# QSPI.net
KiCad netlist of a schematic drawn in Altium Designer
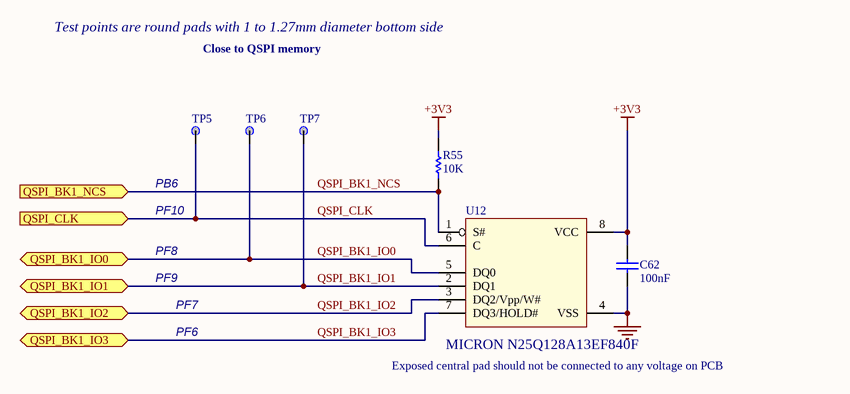
[diagram p0: QSPI.SchDoc]

(export (version "E")
  (design (tool "Eeschema 10.0.6"))
  (components
    (comp (ref "C62")
      (value "100nF")
      (footprint "0402C")
      (description "Capacitor")
      (fields (field (name "PUBLISHER") "Altium Limited"))
      (libsource (lib "Miscellaneous Devices") (part "Cap"))
    )
    (comp (ref "R55")
      (value "10K")
      (footprint "0402R")
      (description "Resistor,10K,0402,1%,YAGEO")
      (libsource (lib "MCD_TOOLS") (part "Res_10K_1%_0402"))
    )
    (comp (ref "TP5") (value "TP") (footprint "TP_C40") (libsource (lib "Almos") (part "TP")))
    (comp (ref "TP6") (value "TP") (footprint "TP_C40") (libsource (lib "Almos") (part "TP")))
    (comp (ref "TP7") (value "TP") (footprint "TP_C40") (libsource (lib "Almos") (part "TP")))
    (comp (ref "U12")
      (value "MICRON N25Q128A13EF840F")
      (footprint "DFN8_1R27_6X8_TP4R8X5R8")
      (description "128Mb, 3V, Multiple I/O Serial Flash Memory, Quad/Dual")
      (libsource (lib "MCD_TOOLS") (part "N25Q128A13EF840E"))
    )
  )
  (nets
    (net (code "1") (name "+3V3") (class "Default")
      (node (ref "C62") (pin "1") (pinfunction "1_1") (pintype "passive"))
      (node (ref "R55") (pin "2") (pinfunction "2_2") (pintype "passive"))
      (node (ref "U12") (pin "8") (pinfunction "VCC_8") (pintype "passive"))
    )
    (net (code "2") (name "/QSPI_BK1_IO0") (class "Default")
      (node (ref "TP6") (pin "1") (pinfunction "1_1") (pintype "passive"))
      (node (ref "U12") (pin "5") (pinfunction "DQ0_5") (pintype "passive"))
    )
    (net (code "3") (name "/QSPI_BK1_IO1") (class "Default")
      (node (ref "TP7") (pin "1") (pinfunction "1_1") (pintype "passive"))
      (node (ref "U12") (pin "2") (pinfunction "DQ1_2") (pintype "passive"))
    )
    (net (code "4") (name "/QSPI_BK1_IO2") (class "Default")
      (node (ref "U12") (pin "3") (pinfunction "DQ2/Vpp/W#_3") (pintype "passive"))
    )
    (net (code "5") (name "/QSPI_BK1_IO3") (class "Default")
      (node (ref "U12") (pin "7") (pinfunction "DQ3/HOLD#_7") (pintype "passive"))
    )
    (net (code "6") (name "/QSPI_BK1_NCS") (class "Default")
      (node (ref "R55") (pin "1") (pinfunction "1_1") (pintype "passive"))
      (node (ref "U12") (pin "1") (pinfunction "S#_1") (pintype "passive"))
    )
    (net (code "7") (name "/QSPI_CLK") (class "Default")
      (node (ref "TP5") (pin "1") (pinfunction "1_1") (pintype "passive"))
      (node (ref "U12") (pin "6") (pinfunction "C_6") (pintype "passive"))
    )
    (net (code "8") (name "GND") (class "Default")
      (node (ref "C62") (pin "2") (pinfunction "2_2") (pintype "passive"))
      (node (ref "U12") (pin "4") (pinfunction "VSS_4") (pintype "passive"))
    )
  )
)
